# control-surface-main.net
KiCad netlist of a schematic drawn in EAGLE
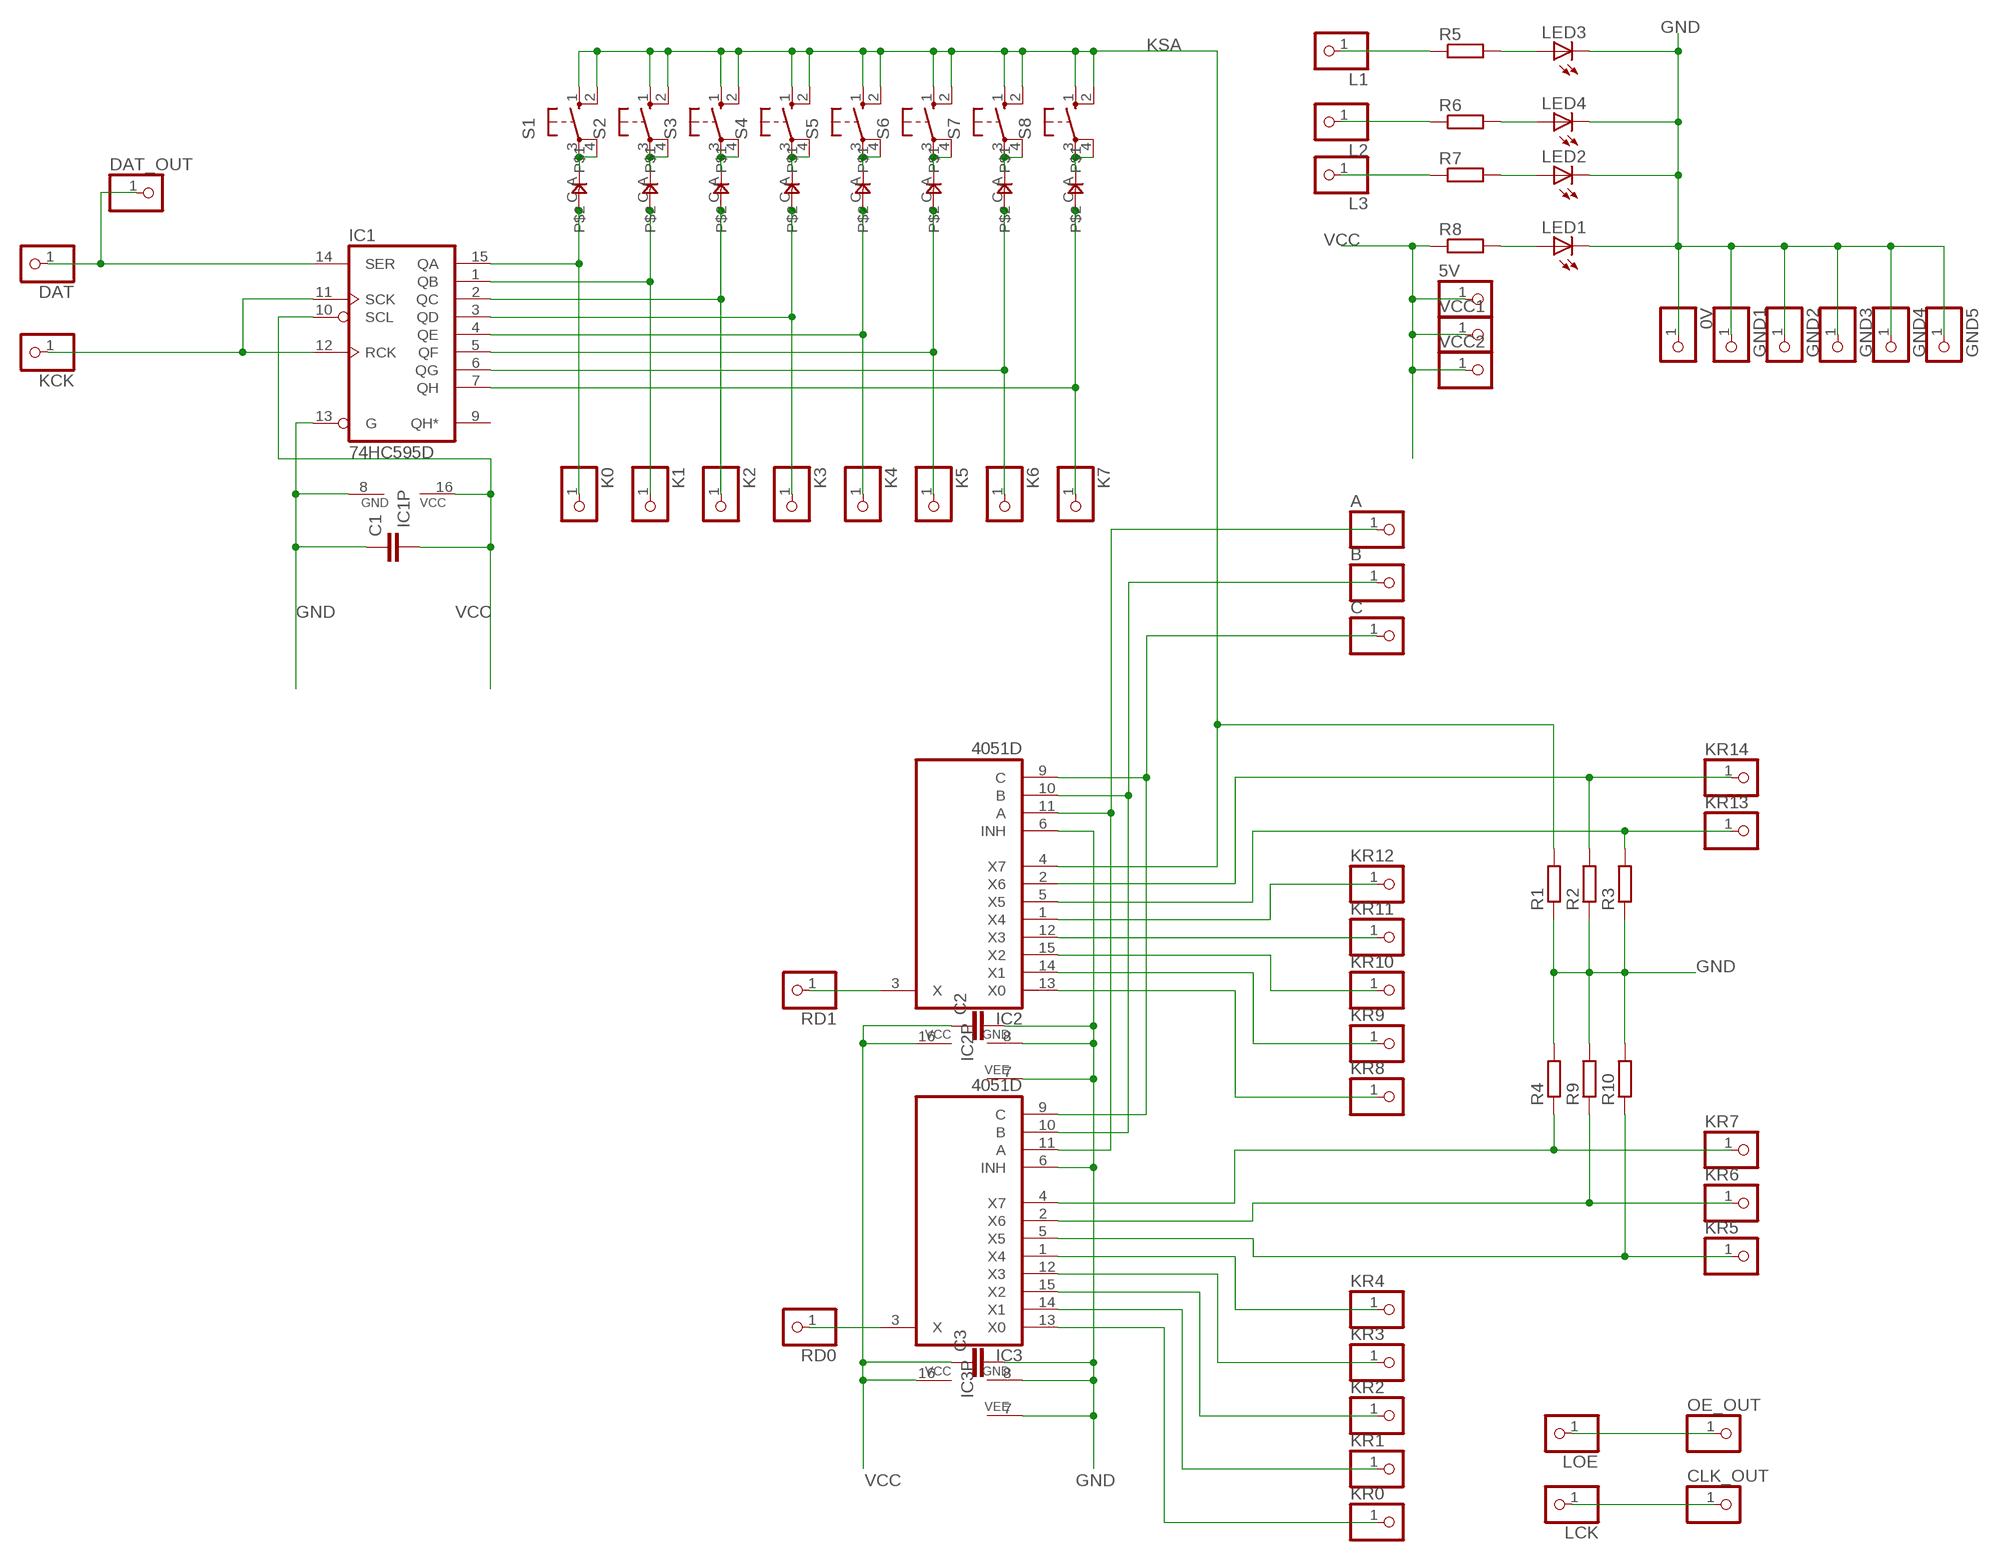
[diagram p0: schematic, sheet 1]

(export (version "E")
  (design (tool "Eeschema 10.0.6"))
  (components
    (comp (ref "0V")
      (value "PINHD-1X1")
      (footprint "eagle-import:1X01")
      (libsource (lib "eagle-import") (part "PINHD-1X1"))
    )
    (comp (ref "5V")
      (value "PINHD-1X1")
      (footprint "eagle-import:1X01")
      (libsource (lib "eagle-import") (part "PINHD-1X1"))
    )
    (comp (ref "A")
      (value "PINHD-1X1")
      (footprint "eagle-import:1X01")
      (libsource (lib "eagle-import") (part "PINHD-1X1"))
    )
    (comp (ref "B")
      (value "PINHD-1X1")
      (footprint "eagle-import:1X01")
      (libsource (lib "eagle-import") (part "PINHD-1X1"))
    )
    (comp (ref "C")
      (value "PINHD-1X1")
      (footprint "eagle-import:1X01")
      (libsource (lib "eagle-import") (part "PINHD-1X1"))
    )
    (comp (ref "C1")
      (value "C-EUC0805")
      (footprint "eagle-import:C0805")
      (libsource (lib "eagle-import") (part "C-EUC0805"))
    )
    (comp (ref "C2")
      (value "C-EUC0805")
      (footprint "eagle-import:C0805")
      (libsource (lib "eagle-import") (part "C-EUC0805"))
    )
    (comp (ref "C3")
      (value "C-EUC0805")
      (footprint "eagle-import:C0805")
      (libsource (lib "eagle-import") (part "C-EUC0805"))
    )
    (comp (ref "CLK_OUT")
      (value "PINHD-1X1")
      (footprint "eagle-import:1X01")
      (libsource (lib "eagle-import") (part "PINHD-1X1"))
    )
    (comp (ref "D1")
      (value "0805DIODE")
      (footprint "eagle-import:0805DIODE")
      (libsource (lib "eagle-import") (part "0805DIODE"))
    )
    (comp (ref "D2")
      (value "0805DIODE")
      (footprint "eagle-import:0805DIODE")
      (libsource (lib "eagle-import") (part "0805DIODE"))
    )
    (comp (ref "D3")
      (value "0805DIODE")
      (footprint "eagle-import:0805DIODE")
      (libsource (lib "eagle-import") (part "0805DIODE"))
    )
    (comp (ref "D4")
      (value "0805DIODE")
      (footprint "eagle-import:0805DIODE")
      (libsource (lib "eagle-import") (part "0805DIODE"))
    )
    (comp (ref "D5")
      (value "0805DIODE")
      (footprint "eagle-import:0805DIODE")
      (libsource (lib "eagle-import") (part "0805DIODE"))
    )
    (comp (ref "D6")
      (value "0805DIODE")
      (footprint "eagle-import:0805DIODE")
      (libsource (lib "eagle-import") (part "0805DIODE"))
    )
    (comp (ref "D7")
      (value "0805DIODE")
      (footprint "eagle-import:0805DIODE")
      (libsource (lib "eagle-import") (part "0805DIODE"))
    )
    (comp (ref "D8")
      (value "0805DIODE")
      (footprint "eagle-import:0805DIODE")
      (libsource (lib "eagle-import") (part "0805DIODE"))
    )
    (comp (ref "DAT")
      (value "PINHD-1X1")
      (footprint "eagle-import:1X01")
      (libsource (lib "eagle-import") (part "PINHD-1X1"))
    )
    (comp (ref "DAT_OUT")
      (value "PINHD-1X1")
      (footprint "eagle-import:1X01")
      (libsource (lib "eagle-import") (part "PINHD-1X1"))
    )
    (comp (ref "GND1")
      (value "PINHD-1X1")
      (footprint "eagle-import:1X01")
      (libsource (lib "eagle-import") (part "PINHD-1X1"))
    )
    (comp (ref "GND2")
      (value "PINHD-1X1")
      (footprint "eagle-import:1X01")
      (libsource (lib "eagle-import") (part "PINHD-1X1"))
    )
    (comp (ref "GND3")
      (value "PINHD-1X1")
      (footprint "eagle-import:1X01")
      (libsource (lib "eagle-import") (part "PINHD-1X1"))
    )
    (comp (ref "GND4")
      (value "PINHD-1X1")
      (footprint "eagle-import:1X01")
      (libsource (lib "eagle-import") (part "PINHD-1X1"))
    )
    (comp (ref "GND5")
      (value "PINHD-1X1")
      (footprint "eagle-import:1X01")
      (libsource (lib "eagle-import") (part "PINHD-1X1"))
    )
    (comp (ref "IC1")
      (value "74HC595D")
      (footprint "eagle-import:SO16")
      (libsource (lib "eagle-import") (part "74595DHC"))
    )
    (comp (ref "IC2")
      (value "4051D")
      (footprint "eagle-import:SO16")
      (libsource (lib "eagle-import") (part "4051D"))
    )
    (comp (ref "IC3")
      (value "4051D")
      (footprint "eagle-import:SO16")
      (libsource (lib "eagle-import") (part "4051D"))
    )
    (comp (ref "K0")
      (value "PINHD-1X1")
      (footprint "eagle-import:1X01")
      (libsource (lib "eagle-import") (part "PINHD-1X1"))
    )
    (comp (ref "K1")
      (value "PINHD-1X1")
      (footprint "eagle-import:1X01")
      (libsource (lib "eagle-import") (part "PINHD-1X1"))
    )
    (comp (ref "K2")
      (value "PINHD-1X1")
      (footprint "eagle-import:1X01")
      (libsource (lib "eagle-import") (part "PINHD-1X1"))
    )
    (comp (ref "K3")
      (value "PINHD-1X1")
      (footprint "eagle-import:1X01")
      (libsource (lib "eagle-import") (part "PINHD-1X1"))
    )
    (comp (ref "K4")
      (value "PINHD-1X1")
      (footprint "eagle-import:1X01")
      (libsource (lib "eagle-import") (part "PINHD-1X1"))
    )
    (comp (ref "K5")
      (value "PINHD-1X1")
      (footprint "eagle-import:1X01")
      (libsource (lib "eagle-import") (part "PINHD-1X1"))
    )
    (comp (ref "K6")
      (value "PINHD-1X1")
      (footprint "eagle-import:1X01")
      (libsource (lib "eagle-import") (part "PINHD-1X1"))
    )
    (comp (ref "K7")
      (value "PINHD-1X1")
      (footprint "eagle-import:1X01")
      (libsource (lib "eagle-import") (part "PINHD-1X1"))
    )
    (comp (ref "KCK")
      (value "PINHD-1X1")
      (footprint "eagle-import:1X01")
      (libsource (lib "eagle-import") (part "PINHD-1X1"))
    )
    (comp (ref "KR0")
      (value "PINHD-1X1")
      (footprint "eagle-import:1X01")
      (libsource (lib "eagle-import") (part "PINHD-1X1"))
    )
    (comp (ref "KR1")
      (value "PINHD-1X1")
      (footprint "eagle-import:1X01")
      (libsource (lib "eagle-import") (part "PINHD-1X1"))
    )
    (comp (ref "KR2")
      (value "PINHD-1X1")
      (footprint "eagle-import:1X01")
      (libsource (lib "eagle-import") (part "PINHD-1X1"))
    )
    (comp (ref "KR3")
      (value "PINHD-1X1")
      (footprint "eagle-import:1X01")
      (libsource (lib "eagle-import") (part "PINHD-1X1"))
    )
    (comp (ref "KR4")
      (value "PINHD-1X1")
      (footprint "eagle-import:1X01")
      (libsource (lib "eagle-import") (part "PINHD-1X1"))
    )
    (comp (ref "KR5")
      (value "PINHD-1X1")
      (footprint "eagle-import:1X01")
      (libsource (lib "eagle-import") (part "PINHD-1X1"))
    )
    (comp (ref "KR6")
      (value "PINHD-1X1")
      (footprint "eagle-import:1X01")
      (libsource (lib "eagle-import") (part "PINHD-1X1"))
    )
    (comp (ref "KR7")
      (value "PINHD-1X1")
      (footprint "eagle-import:1X01")
      (libsource (lib "eagle-import") (part "PINHD-1X1"))
    )
    (comp (ref "KR8")
      (value "PINHD-1X1")
      (footprint "eagle-import:1X01")
      (libsource (lib "eagle-import") (part "PINHD-1X1"))
    )
    (comp (ref "KR9")
      (value "PINHD-1X1")
      (footprint "eagle-import:1X01")
      (libsource (lib "eagle-import") (part "PINHD-1X1"))
    )
    (comp (ref "KR10")
      (value "PINHD-1X1")
      (footprint "eagle-import:1X01")
      (libsource (lib "eagle-import") (part "PINHD-1X1"))
    )
    (comp (ref "KR11")
      (value "PINHD-1X1")
      (footprint "eagle-import:1X01")
      (libsource (lib "eagle-import") (part "PINHD-1X1"))
    )
    (comp (ref "KR12")
      (value "PINHD-1X1")
      (footprint "eagle-import:1X01")
      (libsource (lib "eagle-import") (part "PINHD-1X1"))
    )
    (comp (ref "KR13")
      (value "PINHD-1X1")
      (footprint "eagle-import:1X01")
      (libsource (lib "eagle-import") (part "PINHD-1X1"))
    )
    (comp (ref "KR14")
      (value "PINHD-1X1")
      (footprint "eagle-import:1X01")
      (libsource (lib "eagle-import") (part "PINHD-1X1"))
    )
    (comp (ref "L1")
      (value "PINHD-1X1")
      (footprint "eagle-import:1X01")
      (libsource (lib "eagle-import") (part "PINHD-1X1"))
    )
    (comp (ref "L2")
      (value "PINHD-1X1")
      (footprint "eagle-import:1X01")
      (libsource (lib "eagle-import") (part "PINHD-1X1"))
    )
    (comp (ref "L3")
      (value "PINHD-1X1")
      (footprint "eagle-import:1X01")
      (libsource (lib "eagle-import") (part "PINHD-1X1"))
    )
    (comp (ref "LCK")
      (value "PINHD-1X1")
      (footprint "eagle-import:1X01")
      (libsource (lib "eagle-import") (part "PINHD-1X1"))
    )
    (comp (ref "LED1")
      (value "LED3MM")
      (footprint "eagle-import:LED3MM")
      (libsource (lib "eagle-import") (part "LED3MM"))
    )
    (comp (ref "LED2")
      (value "LED3MM")
      (footprint "eagle-import:LED3MM")
      (libsource (lib "eagle-import") (part "LED3MM"))
    )
    (comp (ref "LED3")
      (value "LED3MM")
      (footprint "eagle-import:LED3MM")
      (libsource (lib "eagle-import") (part "LED3MM"))
    )
    (comp (ref "LED4")
      (value "LED3MM")
      (footprint "eagle-import:LED3MM")
      (libsource (lib "eagle-import") (part "LED3MM"))
    )
    (comp (ref "LOE")
      (value "PINHD-1X1")
      (footprint "eagle-import:1X01")
      (libsource (lib "eagle-import") (part "PINHD-1X1"))
    )
    (comp (ref "OE_OUT")
      (value "PINHD-1X1")
      (footprint "eagle-import:1X01")
      (libsource (lib "eagle-import") (part "PINHD-1X1"))
    )
    (comp (ref "R1")
      (value "R-EU_R0805")
      (footprint "eagle-import:R0805")
      (libsource (lib "eagle-import") (part "R-EU_R0805"))
    )
    (comp (ref "R2")
      (value "R-EU_R0805")
      (footprint "eagle-import:R0805")
      (libsource (lib "eagle-import") (part "R-EU_R0805"))
    )
    (comp (ref "R3")
      (value "R-EU_R0805")
      (footprint "eagle-import:R0805")
      (libsource (lib "eagle-import") (part "R-EU_R0805"))
    )
    (comp (ref "R4")
      (value "R-EU_R0805")
      (footprint "eagle-import:R0805")
      (libsource (lib "eagle-import") (part "R-EU_R0805"))
    )
    (comp (ref "R5")
      (value "R-EU_R0805")
      (footprint "eagle-import:R0805")
      (libsource (lib "eagle-import") (part "R-EU_R0805"))
    )
    (comp (ref "R6")
      (value "R-EU_R0805")
      (footprint "eagle-import:R0805")
      (libsource (lib "eagle-import") (part "R-EU_R0805"))
    )
    (comp (ref "R7")
      (value "R-EU_R0805")
      (footprint "eagle-import:R0805")
      (libsource (lib "eagle-import") (part "R-EU_R0805"))
    )
    (comp (ref "R8")
      (value "R-EU_R0805")
      (footprint "eagle-import:R0805")
      (libsource (lib "eagle-import") (part "R-EU_R0805"))
    )
    (comp (ref "R9")
      (value "R-EU_R0805")
      (footprint "eagle-import:R0805")
      (libsource (lib "eagle-import") (part "R-EU_R0805"))
    )
    (comp (ref "R10")
      (value "R-EU_R0805")
      (footprint "eagle-import:R0805")
      (libsource (lib "eagle-import") (part "R-EU_R0805"))
    )
    (comp (ref "RD0")
      (value "PINHD-1X1")
      (footprint "eagle-import:1X01")
      (libsource (lib "eagle-import") (part "PINHD-1X1"))
    )
    (comp (ref "RD1")
      (value "PINHD-1X1")
      (footprint "eagle-import:1X01")
      (libsource (lib "eagle-import") (part "PINHD-1X1"))
    )
    (comp (ref "S1")
      (value "40-XX")
      (footprint "eagle-import:B3F-40XX")
      (fields (field (name "MF") "OMRON COMPONENTS USA") (field (name "MPN") "B3F-4000"))
      (libsource (lib "eagle-import") (part "40-XX"))
    )
    (comp (ref "S2")
      (value "40-XX")
      (footprint "eagle-import:B3F-40XX")
      (fields (field (name "MF") "OMRON COMPONENTS USA") (field (name "MPN") "B3F-4000"))
      (libsource (lib "eagle-import") (part "40-XX"))
    )
    (comp (ref "S3")
      (value "40-XX")
      (footprint "eagle-import:B3F-40XX")
      (fields (field (name "MF") "OMRON COMPONENTS USA") (field (name "MPN") "B3F-4000"))
      (libsource (lib "eagle-import") (part "40-XX"))
    )
    (comp (ref "S4")
      (value "40-XX")
      (footprint "eagle-import:B3F-40XX")
      (fields (field (name "MF") "OMRON COMPONENTS USA") (field (name "MPN") "B3F-4000"))
      (libsource (lib "eagle-import") (part "40-XX"))
    )
    (comp (ref "S5")
      (value "40-XX")
      (footprint "eagle-import:B3F-40XX")
      (fields (field (name "MF") "OMRON COMPONENTS USA") (field (name "MPN") "B3F-4000"))
      (libsource (lib "eagle-import") (part "40-XX"))
    )
    (comp (ref "S6")
      (value "40-XX")
      (footprint "eagle-import:B3F-40XX")
      (fields (field (name "MF") "OMRON COMPONENTS USA") (field (name "MPN") "B3F-4000"))
      (libsource (lib "eagle-import") (part "40-XX"))
    )
    (comp (ref "S7")
      (value "40-XX")
      (footprint "eagle-import:B3F-40XX")
      (fields (field (name "MF") "OMRON COMPONENTS USA") (field (name "MPN") "B3F-4000"))
      (libsource (lib "eagle-import") (part "40-XX"))
    )
    (comp (ref "S8")
      (value "40-XX")
      (footprint "eagle-import:B3F-40XX")
      (fields (field (name "MF") "OMRON COMPONENTS USA") (field (name "MPN") "B3F-4000"))
      (libsource (lib "eagle-import") (part "40-XX"))
    )
    (comp (ref "VCC1")
      (value "PINHD-1X1")
      (footprint "eagle-import:1X01")
      (libsource (lib "eagle-import") (part "PINHD-1X1"))
    )
    (comp (ref "VCC2")
      (value "PINHD-1X1")
      (footprint "eagle-import:1X01")
      (libsource (lib "eagle-import") (part "PINHD-1X1"))
    )
  )
  (nets
    (net (code "1") (name "/GND") (class "Default")
      (node (ref "0V") (pin "1") (pinfunction "1_1") (pintype "passive"))
      (node (ref "C1") (pin "1") (pinfunction "1_1") (pintype "passive"))
      (node (ref "C2") (pin "2") (pinfunction "2_2") (pintype "passive"))
      (node (ref "C3") (pin "2") (pinfunction "2_2") (pintype "passive"))
      (node (ref "GND1") (pin "1") (pinfunction "1_1") (pintype "passive"))
      (node (ref "GND2") (pin "1") (pinfunction "1_1") (pintype "passive"))
      (node (ref "GND3") (pin "1") (pinfunction "1_1") (pintype "passive"))
      (node (ref "GND4") (pin "1") (pinfunction "1_1") (pintype "passive"))
      (node (ref "GND5") (pin "1") (pinfunction "1_1") (pintype "passive"))
      (node (ref "IC1") (pin "13") (pinfunction "G_13") (pintype "input"))
      (node (ref "IC1") (pin "8") (pinfunction "GND_8") (pintype "power_in"))
      (node (ref "IC2") (pin "6") (pinfunction "INH_6") (pintype "input"))
      (node (ref "IC2") (pin "7") (pinfunction "VEE_7") (pintype "power_in"))
      (node (ref "IC2") (pin "8") (pinfunction "GND_8") (pintype "power_in"))
      (node (ref "IC3") (pin "6") (pinfunction "INH_6") (pintype "input"))
      (node (ref "IC3") (pin "7") (pinfunction "VEE_7") (pintype "power_in"))
      (node (ref "IC3") (pin "8") (pinfunction "GND_8") (pintype "power_in"))
      (node (ref "LED1") (pin "K") (pinfunction "C_K") (pintype "passive"))
      (node (ref "LED2") (pin "K") (pinfunction "C_K") (pintype "passive"))
      (node (ref "LED3") (pin "K") (pinfunction "C_K") (pintype "passive"))
      (node (ref "LED4") (pin "K") (pinfunction "C_K") (pintype "passive"))
      (node (ref "R1") (pin "1") (pinfunction "1_1") (pintype "passive"))
      (node (ref "R10") (pin "2") (pinfunction "2_2") (pintype "passive"))
      (node (ref "R2") (pin "1") (pinfunction "1_1") (pintype "passive"))
      (node (ref "R3") (pin "1") (pinfunction "1_1") (pintype "passive"))
      (node (ref "R4") (pin "2") (pinfunction "2_2") (pintype "passive"))
      (node (ref "R9") (pin "2") (pinfunction "2_2") (pintype "passive"))
    )
    (net (code "2") (name "/KSA") (class "Default")
      (node (ref "IC2") (pin "4") (pinfunction "X7_4") (pintype "bidirectional"))
      (node (ref "R1") (pin "2") (pinfunction "2_2") (pintype "passive"))
      (node (ref "S1") (pin "1") (pinfunction "S_1") (pintype "passive"))
      (node (ref "S1") (pin "2") (pinfunction "S1_2") (pintype "passive"))
      (node (ref "S2") (pin "1") (pinfunction "S_1") (pintype "passive"))
      (node (ref "S2") (pin "2") (pinfunction "S1_2") (pintype "passive"))
      (node (ref "S3") (pin "1") (pinfunction "S_1") (pintype "passive"))
      (node (ref "S3") (pin "2") (pinfunction "S1_2") (pintype "passive"))
      (node (ref "S4") (pin "1") (pinfunction "S_1") (pintype "passive"))
      (node (ref "S4") (pin "2") (pinfunction "S1_2") (pintype "passive"))
      (node (ref "S5") (pin "1") (pinfunction "S_1") (pintype "passive"))
      (node (ref "S5") (pin "2") (pinfunction "S1_2") (pintype "passive"))
      (node (ref "S6") (pin "1") (pinfunction "S_1") (pintype "passive"))
      (node (ref "S6") (pin "2") (pinfunction "S1_2") (pintype "passive"))
      (node (ref "S7") (pin "1") (pinfunction "S_1") (pintype "passive"))
      (node (ref "S7") (pin "2") (pinfunction "S1_2") (pintype "passive"))
      (node (ref "S8") (pin "1") (pinfunction "S_1") (pintype "passive"))
      (node (ref "S8") (pin "2") (pinfunction "S1_2") (pintype "passive"))
    )
    (net (code "3") (name "/VCC") (class "Default")
      (node (ref "5V") (pin "1") (pinfunction "1_1") (pintype "passive"))
      (node (ref "C1") (pin "2") (pinfunction "2_2") (pintype "passive"))
      (node (ref "C2") (pin "1") (pinfunction "1_1") (pintype "passive"))
      (node (ref "C3") (pin "1") (pinfunction "1_1") (pintype "passive"))
      (node (ref "IC1") (pin "10") (pinfunction "SCL_10") (pintype "input"))
      (node (ref "IC1") (pin "16") (pinfunction "VCC_16") (pintype "power_in"))
      (node (ref "IC2") (pin "16") (pinfunction "VCC_16") (pintype "power_in"))
      (node (ref "IC3") (pin "16") (pinfunction "VCC_16") (pintype "power_in"))
      (node (ref "R8") (pin "1") (pinfunction "1_1") (pintype "passive"))
      (node (ref "VCC1") (pin "1") (pinfunction "1_1") (pintype "passive"))
      (node (ref "VCC2") (pin "1") (pinfunction "1_1") (pintype "passive"))
    )
    (net (code "4") (name "Net-(CLK_OUT-Pad1)") (class "Default")
      (node (ref "CLK_OUT") (pin "1") (pinfunction "1_1") (pintype "passive"))
      (node (ref "LCK") (pin "1") (pinfunction "1_1") (pintype "passive"))
    )
    (net (code "5") (name "Net-(D1-P$1)") (class "Default")
      (node (ref "D1") (pin "C") (pinfunction "P$1_C") (pintype "bidirectional"))
      (node (ref "IC1") (pin "3") (pinfunction "QD_3") (pintype "tri_state"))
      (node (ref "K3") (pin "1") (pinfunction "1_1") (pintype "passive"))
    )
    (net (code "6") (name "Net-(D1-P$2)") (class "Default")
      (node (ref "D1") (pin "A") (pinfunction "P$2_A") (pintype "bidirectional"))
      (node (ref "S4") (pin "3") (pinfunction "P_3") (pintype "passive"))
      (node (ref "S4") (pin "4") (pinfunction "P1_4") (pintype "passive"))
    )
    (net (code "7") (name "Net-(D2-P$1)") (class "Default")
      (node (ref "D2") (pin "C") (pinfunction "P$1_C") (pintype "bidirectional"))
      (node (ref "IC1") (pin "4") (pinfunction "QE_4") (pintype "tri_state"))
      (node (ref "K4") (pin "1") (pinfunction "1_1") (pintype "passive"))
    )
    (net (code "8") (name "Net-(D2-P$2)") (class "Default")
      (node (ref "D2") (pin "A") (pinfunction "P$2_A") (pintype "bidirectional"))
      (node (ref "S5") (pin "3") (pinfunction "P_3") (pintype "passive"))
      (node (ref "S5") (pin "4") (pinfunction "P1_4") (pintype "passive"))
    )
    (net (code "9") (name "Net-(D3-P$1)") (class "Default")
      (node (ref "D3") (pin "C") (pinfunction "P$1_C") (pintype "bidirectional"))
      (node (ref "IC1") (pin "5") (pinfunction "QF_5") (pintype "tri_state"))
      (node (ref "K5") (pin "1") (pinfunction "1_1") (pintype "passive"))
    )
    (net (code "10") (name "Net-(D3-P$2)") (class "Default")
      (node (ref "D3") (pin "A") (pinfunction "P$2_A") (pintype "bidirectional"))
      (node (ref "S6") (pin "3") (pinfunction "P_3") (pintype "passive"))
      (node (ref "S6") (pin "4") (pinfunction "P1_4") (pintype "passive"))
    )
    (net (code "11") (name "Net-(D4-P$1)") (class "Default")
      (node (ref "D4") (pin "C") (pinfunction "P$1_C") (pintype "bidirectional"))
      (node (ref "IC1") (pin "6") (pinfunction "QG_6") (pintype "tri_state"))
      (node (ref "K6") (pin "1") (pinfunction "1_1") (pintype "passive"))
    )
    (net (code "12") (name "Net-(D4-P$2)") (class "Default")
      (node (ref "D4") (pin "A") (pinfunction "P$2_A") (pintype "bidirectional"))
      (node (ref "S7") (pin "3") (pinfunction "P_3") (pintype "passive"))
      (node (ref "S7") (pin "4") (pinfunction "P1_4") (pintype "passive"))
    )
    (net (code "13") (name "Net-(D5-P$1)") (class "Default")
      (node (ref "D5") (pin "C") (pinfunction "P$1_C") (pintype "bidirectional"))
      (node (ref "IC1") (pin "7") (pinfunction "QH_7") (pintype "tri_state"))
      (node (ref "K7") (pin "1") (pinfunction "1_1") (pintype "passive"))
    )
    (net (code "14") (name "Net-(D5-P$2)") (class "Default")
      (node (ref "D5") (pin "A") (pinfunction "P$2_A") (pintype "bidirectional"))
      (node (ref "S8") (pin "3") (pinfunction "P_3") (pintype "passive"))
      (node (ref "S8") (pin "4") (pinfunction "P1_4") (pintype "passive"))
    )
    (net (code "15") (name "Net-(D6-P$1)") (class "Default")
      (node (ref "D6") (pin "C") (pinfunction "P$1_C") (pintype "bidirectional"))
      (node (ref "IC1") (pin "15") (pinfunction "QA_15") (pintype "tri_state"))
      (node (ref "K0") (pin "1") (pinfunction "1_1") (pintype "passive"))
    )
    (net (code "16") (name "Net-(D6-P$2)") (class "Default")
      (node (ref "D6") (pin "A") (pinfunction "P$2_A") (pintype "bidirectional"))
      (node (ref "S1") (pin "3") (pinfunction "P_3") (pintype "passive"))
      (node (ref "S1") (pin "4") (pinfunction "P1_4") (pintype "passive"))
    )
    (net (code "17") (name "Net-(D7-P$1)") (class "Default")
      (node (ref "D7") (pin "C") (pinfunction "P$1_C") (pintype "bidirectional"))
      (node (ref "IC1") (pin "1") (pinfunction "QB_1") (pintype "tri_state"))
      (node (ref "K1") (pin "1") (pinfunction "1_1") (pintype "passive"))
    )
    (net (code "18") (name "Net-(D7-P$2)") (class "Default")
      (node (ref "D7") (pin "A") (pinfunction "P$2_A") (pintype "bidirectional"))
      (node (ref "S2") (pin "3") (pinfunction "P_3") (pintype "passive"))
      (node (ref "S2") (pin "4") (pinfunction "P1_4") (pintype "passive"))
    )
    (net (code "19") (name "Net-(D8-P$1)") (class "Default")
      (node (ref "D8") (pin "C") (pinfunction "P$1_C") (pintype "bidirectional"))
      (node (ref "IC1") (pin "2") (pinfunction "QC_2") (pintype "tri_state"))
      (node (ref "K2") (pin "1") (pinfunction "1_1") (pintype "passive"))
    )
    (net (code "20") (name "Net-(D8-P$2)") (class "Default")
      (node (ref "D8") (pin "A") (pinfunction "P$2_A") (pintype "bidirectional"))
      (node (ref "S3") (pin "3") (pinfunction "P_3") (pintype "passive"))
      (node (ref "S3") (pin "4") (pinfunction "P1_4") (pintype "passive"))
    )
    (net (code "21") (name "Net-(IC1A-RCK)") (class "Default")
      (node (ref "IC1") (pin "11") (pinfunction "SCK_11") (pintype "input"))
      (node (ref "IC1") (pin "12") (pinfunction "RCK_12") (pintype "input"))
      (node (ref "KCK") (pin "1") (pinfunction "1_1") (pintype "passive"))
    )
    (net (code "22") (name "Net-(IC1A-SER)") (class "Default")
      (node (ref "DAT") (pin "1") (pinfunction "1_1") (pintype "passive"))
      (node (ref "DAT_OUT") (pin "1") (pinfunction "1_1") (pintype "passive"))
      (node (ref "IC1") (pin "14") (pinfunction "SER_14") (pintype "input"))
    )
    (net (code "23") (name "Net-(IC2A-A)") (class "Default")
      (node (ref "A") (pin "1") (pinfunction "1_1") (pintype "passive"))
      (node (ref "IC2") (pin "11") (pinfunction "A_11") (pintype "input"))
      (node (ref "IC3") (pin "11") (pinfunction "A_11") (pintype "input"))
    )
    (net (code "24") (name "Net-(IC2A-B)") (class "Default")
      (node (ref "B") (pin "1") (pinfunction "1_1") (pintype "passive"))
      (node (ref "IC2") (pin "10") (pinfunction "B_10") (pintype "input"))
      (node (ref "IC3") (pin "10") (pinfunction "B_10") (pintype "input"))
    )
    (net (code "25") (name "Net-(IC2A-C)") (class "Default")
      (node (ref "C") (pin "1") (pinfunction "1_1") (pintype "passive"))
      (node (ref "IC2") (pin "9") (pinfunction "C_9") (pintype "input"))
      (node (ref "IC3") (pin "9") (pinfunction "C_9") (pintype "input"))
    )
    (net (code "26") (name "Net-(IC2A-X)") (class "Default")
      (node (ref "IC2") (pin "3") (pinfunction "X_3") (pintype "bidirectional"))
      (node (ref "RD1") (pin "1") (pinfunction "1_1") (pintype "passive"))
    )
    (net (code "27") (name "Net-(IC2A-X0)") (class "Default")
      (node (ref "IC2") (pin "13") (pinfunction "X0_13") (pintype "bidirectional"))
      (node (ref "KR8") (pin "1") (pinfunction "1_1") (pintype "passive"))
    )
    (net (code "28") (name "Net-(IC2A-X1)") (class "Default")
      (node (ref "IC2") (pin "14") (pinfunction "X1_14") (pintype "bidirectional"))
      (node (ref "KR9") (pin "1") (pinfunction "1_1") (pintype "passive"))
    )
    (net (code "29") (name "Net-(IC2A-X2)") (class "Default")
      (node (ref "IC2") (pin "15") (pinfunction "X2_15") (pintype "bidirectional"))
      (node (ref "KR10") (pin "1") (pinfunction "1_1") (pintype "passive"))
    )
    (net (code "30") (name "Net-(IC2A-X3)") (class "Default")
      (node (ref "IC2") (pin "12") (pinfunction "X3_12") (pintype "bidirectional"))
      (node (ref "KR11") (pin "1") (pinfunction "1_1") (pintype "passive"))
    )
    (net (code "31") (name "Net-(IC2A-X4)") (class "Default")
      (node (ref "IC2") (pin "1") (pinfunction "X4_1") (pintype "bidirectional"))
      (node (ref "KR12") (pin "1") (pinfunction "1_1") (pintype "passive"))
    )
    (net (code "32") (name "Net-(IC2A-X5)") (class "Default")
      (node (ref "IC2") (pin "5") (pinfunction "X5_5") (pintype "bidirectional"))
      (node (ref "KR13") (pin "1") (pinfunction "1_1") (pintype "passive"))
      (node (ref "R3") (pin "2") (pinfunction "2_2") (pintype "passive"))
    )
    (net (code "33") (name "Net-(IC2A-X6)") (class "Default")
      (node (ref "IC2") (pin "2") (pinfunction "X6_2") (pintype "bidirectional"))
      (node (ref "KR14") (pin "1") (pinfunction "1_1") (pintype "passive"))
      (node (ref "R2") (pin "2") (pinfunction "2_2") (pintype "passive"))
    )
    (net (code "34") (name "Net-(IC3A-X)") (class "Default")
      (node (ref "IC3") (pin "3") (pinfunction "X_3") (pintype "bidirectional"))
      (node (ref "RD0") (pin "1") (pinfunction "1_1") (pintype "passive"))
    )
    (net (code "35") (name "Net-(IC3A-X0)") (class "Default")
      (node (ref "IC3") (pin "13") (pinfunction "X0_13") (pintype "bidirectional"))
      (node (ref "KR0") (pin "1") (pinfunction "1_1") (pintype "passive"))
    )
    (net (code "36") (name "Net-(IC3A-X1)") (class "Default")
      (node (ref "IC3") (pin "14") (pinfunction "X1_14") (pintype "bidirectional"))
      (node (ref "KR1") (pin "1") (pinfunction "1_1") (pintype "passive"))
    )
    (net (code "37") (name "Net-(IC3A-X2)") (class "Default")
      (node (ref "IC3") (pin "15") (pinfunction "X2_15") (pintype "bidirectional"))
      (node (ref "KR2") (pin "1") (pinfunction "1_1") (pintype "passive"))
    )
    (net (code "38") (name "Net-(IC3A-X3)") (class "Default")
      (node (ref "IC3") (pin "12") (pinfunction "X3_12") (pintype "bidirectional"))
      (node (ref "KR3") (pin "1") (pinfunction "1_1") (pintype "passive"))
    )
    (net (code "39") (name "Net-(IC3A-X4)") (class "Default")
      (node (ref "IC3") (pin "1") (pinfunction "X4_1") (pintype "bidirectional"))
      (node (ref "KR4") (pin "1") (pinfunction "1_1") (pintype "passive"))
    )
    (net (code "40") (name "Net-(IC3A-X5)") (class "Default")
      (node (ref "IC3") (pin "5") (pinfunction "X5_5") (pintype "bidirectional"))
      (node (ref "KR5") (pin "1") (pinfunction "1_1") (pintype "passive"))
      (node (ref "R10") (pin "1") (pinfunction "1_1") (pintype "passive"))
    )
    (net (code "41") (name "Net-(IC3A-X6)") (class "Default")
      (node (ref "IC3") (pin "2") (pinfunction "X6_2") (pintype "bidirectional"))
      (node (ref "KR6") (pin "1") (pinfunction "1_1") (pintype "passive"))
      (node (ref "R9") (pin "1") (pinfunction "1_1") (pintype "passive"))
    )
    (net (code "42") (name "Net-(IC3A-X7)") (class "Default")
      (node (ref "IC3") (pin "4") (pinfunction "X7_4") (pintype "bidirectional"))
      (node (ref "KR7") (pin "1") (pinfunction "1_1") (pintype "passive"))
      (node (ref "R4") (pin "1") (pinfunction "1_1") (pintype "passive"))
    )
    (net (code "43") (name "Net-(L1-Pad1)") (class "Default")
      (node (ref "L1") (pin "1") (pinfunction "1_1") (pintype "passive"))
      (node (ref "R5") (pin "1") (pinfunction "1_1") (pintype "passive"))
    )
    (net (code "44") (name "Net-(L2-Pad1)") (class "Default")
      (node (ref "L2") (pin "1") (pinfunction "1_1") (pintype "passive"))
      (node (ref "R6") (pin "1") (pinfunction "1_1") (pintype "passive"))
    )
    (net (code "45") (name "Net-(L3-Pad1)") (class "Default")
      (node (ref "L3") (pin "1") (pinfunction "1_1") (pintype "passive"))
      (node (ref "R7") (pin "1") (pinfunction "1_1") (pintype "passive"))
    )
    (net (code "46") (name "Net-(LED1-PadA)") (class "Default")
      (node (ref "LED1") (pin "A") (pinfunction "A_A") (pintype "passive"))
      (node (ref "R8") (pin "2") (pinfunction "2_2") (pintype "passive"))
    )
    (net (code "47") (name "Net-(LED2-PadA)") (class "Default")
      (node (ref "LED2") (pin "A") (pinfunction "A_A") (pintype "passive"))
      (node (ref "R7") (pin "2") (pinfunction "2_2") (pintype "passive"))
    )
    (net (code "48") (name "Net-(LED3-PadA)") (class "Default")
      (node (ref "LED3") (pin "A") (pinfunction "A_A") (pintype "passive"))
      (node (ref "R5") (pin "2") (pinfunction "2_2") (pintype "passive"))
    )
    (net (code "49") (name "Net-(LED4-PadA)") (class "Default")
      (node (ref "LED4") (pin "A") (pinfunction "A_A") (pintype "passive"))
      (node (ref "R6") (pin "2") (pinfunction "2_2") (pintype "passive"))
    )
    (net (code "50") (name "Net-(LOE-Pad1)") (class "Default")
      (node (ref "LOE") (pin "1") (pinfunction "1_1") (pintype "passive"))
      (node (ref "OE_OUT") (pin "1") (pinfunction "1_1") (pintype "passive"))
    )
    (net (code "51") (name "unconnected-(IC1A-QH*-Pad9)") (class "Default")
      (node (ref "IC1") (pin "9") (pinfunction "QH*_9") (pintype "tri_state"))
    )
  )
)
